# Relay_USBtoUART.net
KiCad netlist of a schematic drawn in Altium Designer
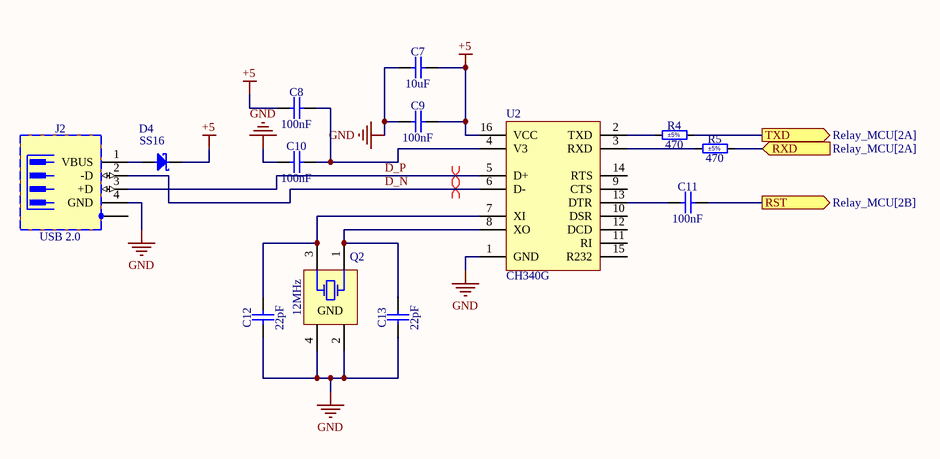
[diagram p0: Relay_USBtoUART.SchDoc]

(export (version "E")
  (design (tool "Eeschema 10.0.6"))
  (components
    (comp (ref "C7")
      (value "10uF")
      (footprint "CAPC2012X135N")
      (description "Non-polarised capacitor")
      (fields
        (field (name "PART NUMBER") "CC0805_10UF_10V_10%_X7R")
        (field (name "VOLTAGE") "10V")
        (field (name "AUTHOR") "CERN DEM JLC")
      )
      (libsource (lib "Capacitors") (part "Capacitor - non polarized"))
    )
    (comp (ref "C8")
      (value "100nF")
      (footprint "CAPC2012X135N")
      (description "Non-polarised capacitor")
      (fields
        (field (name "PART NUMBER") "CC0805_100NF_50V_10%_X7R")
        (field (name "VOLTAGE") "50V")
        (field (name "AUTHOR") "CERN DEM JLC")
      )
      (libsource (lib "Capacitors") (part "Capacitor - non polarized"))
    )
    (comp (ref "C9")
      (value "100nF")
      (footprint "CAPC2012X135N")
      (description "Non-polarised capacitor")
      (fields
        (field (name "PART NUMBER") "CC0805_100NF_50V_10%_X7R")
        (field (name "VOLTAGE") "50V")
        (field (name "AUTHOR") "CERN DEM JLC")
      )
      (libsource (lib "Capacitors") (part "Capacitor - non polarized"))
    )
    (comp (ref "C10")
      (value "100nF")
      (footprint "CAPC2012X135N")
      (description "Non-polarised capacitor")
      (fields
        (field (name "PART NUMBER") "CC0805_100NF_50V_10%_X7R")
        (field (name "VOLTAGE") "50V")
        (field (name "AUTHOR") "CERN DEM JLC")
      )
      (libsource (lib "Capacitors") (part "Capacitor - non polarized"))
    )
    (comp (ref "C11")
      (value "100nF")
      (footprint "CAPC2012X135N")
      (description "Non-polarised capacitor")
      (fields
        (field (name "PART NUMBER") "CC0805_100NF_50V_10%_X7R")
        (field (name "VOLTAGE") "50V")
        (field (name "AUTHOR") "CERN DEM JLC")
      )
      (libsource (lib "Capacitors") (part "Capacitor - non polarized"))
    )
    (comp (ref "C12")
      (value "22pF")
      (footprint "CAPC2012X88N")
      (description "Non-polarised capacitor")
      (fields
        (field (name "PART NUMBER") "CC0805_22PF_200V_5%_C0G")
        (field (name "VOLTAGE") "200V")
        (field (name "AUTHOR") "CERN DEM MR")
      )
      (libsource (lib "Capacitors") (part "Capacitor - non polarized"))
    )
    (comp (ref "C13")
      (value "22pF")
      (footprint "CAPC2012X88N")
      (description "Non-polarised capacitor")
      (fields
        (field (name "PART NUMBER") "CC0805_22PF_200V_5%_C0G")
        (field (name "VOLTAGE") "200V")
        (field (name "AUTHOR") "CERN DEM MR")
      )
      (libsource (lib "Capacitors") (part "Capacitor - non polarized"))
    )
    (comp (ref "D4")
      (value "SS16")
      (footprint "DIOM5127X229N")
      (description "Schottky Diode")
      (fields
        (field (name "VOLTAGE") "60V")
        (field (name "POWER") "1A")
        (field (name "AUTHOR") "CERN DEM JLC")
      )
      (libsource (lib "ICs And Semiconductors") (part "Diode Schottky"))
    )
    (comp (ref "J2")
      (value "USB 2.0")
      (footprint "ASSMANN_A-USBSB")
      (description "4 Pin + 1 Shield USB Receptacle")
      (fields
        (field (name "PART NUMBER") "ASSMANN_A-USBSB")
        (field (name "MANUFACTURER") "ASSMANN")
        (field (name "AUTHOR") "CERN DEM JLC")
      )
      (libsource (lib "Connectors") (part "Connector USB 4 Pin + 1Shield"))
    )
    (comp (ref "Q2")
      (value "12MHz")
      (footprint "XTAL_EPSON_TSX-3225")
      (description "Crystal 4 pins 1=XTAL Control 2=GND3=XTAL 4=GND")
      (fields
        (field (name "PART NUMBER") "XTAL_12MHZ_EPSON_TSX-3225 12.0000MF10Z-B6")
        (field (name "MANUFACTURER") "EPSON")
        (field (name "AUTHOR") "CERN DEM HF")
      )
      (libsource (lib "ICs And Semiconductors") (part "Quartz Crystal 1X 2GND 3X 4GND"))
    )
    (comp (ref "R4")
      (value "470")
      (footprint "RESC2012X60N")
      (description "Resistor - 5%")
      (fields
        (field (name "TOLERANCE") "±5%")
        (field (name "PART NUMBER") "R0805_470R_5%_0.125W_100PPM")
        (field (name "POWER") "0.125W")
        (field (name "AUTHOR") "CERN DEM JLC")
      )
      (libsource (lib "Resistors") (part "Resistor - 1%"))
    )
    (comp (ref "R5")
      (value "470")
      (footprint "RESC2012X60N")
      (description "Resistor - 5%")
      (fields
        (field (name "TOLERANCE") "±5%")
        (field (name "PART NUMBER") "R0805_470R_5%_0.125W_100PPM")
        (field (name "POWER") "0.125W")
        (field (name "AUTHOR") "CERN DEM JLC")
      )
      (libsource (lib "Resistors") (part "Resistor - 1%"))
    )
    (comp (ref "U2")
      (value "CH340G")
      (footprint "SOIC-16")
      (description "USB to UART Converter SOP16")
      (libsource (lib "IKU-LIB") (part "CH340G"))
    )
  )
  (nets
    (net (code "1") (name "+5") (class "Default")
      (node (ref "C7") (pin "2") (pinfunction "2_2") (pintype "passive"))
      (node (ref "C8") (pin "1") (pinfunction "1_1") (pintype "passive"))
      (node (ref "C9") (pin "2") (pinfunction "2_2") (pintype "passive"))
      (node (ref "D4") (pin "1") (pinfunction "C_1") (pintype "passive"))
      (node (ref "U2") (pin "16") (pinfunction "VCC_16") (pintype "passive"))
    )
    (net (code "2") (name "/D_N") (class "Default")
      (node (ref "J2") (pin "2") (pinfunction "-D_2") (pintype "bidirectional"))
      (node (ref "U2") (pin "6") (pinfunction "D-_6") (pintype "passive"))
    )
    (net (code "3") (name "/D_P") (class "Default")
      (node (ref "J2") (pin "3") (pinfunction "+D_3") (pintype "bidirectional"))
      (node (ref "U2") (pin "5") (pinfunction "D+_5") (pintype "passive"))
    )
    (net (code "4") (name "/RST") (class "Default")
      (node (ref "C11") (pin "2") (pinfunction "2_2") (pintype "passive"))
    )
    (net (code "5") (name "/RXD") (class "Default")
      (node (ref "R5") (pin "2") (pinfunction "2_2") (pintype "passive"))
    )
    (net (code "6") (name "/TXD") (class "Default")
      (node (ref "R4") (pin "2") (pinfunction "2_2") (pintype "passive"))
    )
    (net (code "7") (name "GND") (class "Default")
      (node (ref "C10") (pin "1") (pinfunction "1_1") (pintype "passive"))
      (node (ref "C12") (pin "1") (pinfunction "1_1") (pintype "passive"))
      (node (ref "C13") (pin "1") (pinfunction "1_1") (pintype "passive"))
      (node (ref "C7") (pin "1") (pinfunction "1_1") (pintype "passive"))
      (node (ref "C9") (pin "1") (pinfunction "1_1") (pintype "passive"))
      (node (ref "J2") (pin "4") (pinfunction "GND_4") (pintype "power_in"))
      (node (ref "Q2") (pin "2") (pinfunction "GND_2") (pintype "power_in"))
      (node (ref "Q2") (pin "4") (pinfunction "GND_4") (pintype "power_in"))
      (node (ref "U2") (pin "1") (pinfunction "GND_1") (pintype "passive"))
    )
    (net (code "8") (name "Net-(D4-A)") (class "Default")
      (node (ref "D4") (pin "2") (pinfunction "A_2") (pintype "passive"))
      (node (ref "J2") (pin "1") (pinfunction "VBUS_1") (pintype "power_in"))
    )
    (net (code "9") (name "Net-(U2-DTR)") (class "Default")
      (node (ref "C11") (pin "1") (pinfunction "1_1") (pintype "passive"))
      (node (ref "U2") (pin "13") (pinfunction "DTR_13") (pintype "passive"))
    )
    (net (code "10") (name "Net-(U2-RXD)") (class "Default")
      (node (ref "R5") (pin "1") (pinfunction "1_1") (pintype "passive"))
      (node (ref "U2") (pin "3") (pinfunction "RXD_3") (pintype "passive"))
    )
    (net (code "11") (name "Net-(U2-TXD)") (class "Default")
      (node (ref "R4") (pin "1") (pinfunction "1_1") (pintype "passive"))
      (node (ref "U2") (pin "2") (pinfunction "TXD_2") (pintype "passive"))
    )
    (net (code "12") (name "Net-(U2-V3)") (class "Default")
      (node (ref "C10") (pin "2") (pinfunction "2_2") (pintype "passive"))
      (node (ref "C8") (pin "2") (pinfunction "2_2") (pintype "passive"))
      (node (ref "U2") (pin "4") (pinfunction "V3_4") (pintype "passive"))
    )
    (net (code "13") (name "Net-(U2-XI)") (class "Default")
      (node (ref "C12") (pin "2") (pinfunction "2_2") (pintype "passive"))
      (node (ref "Q2") (pin "3") (pinfunction "X_3") (pintype "passive"))
      (node (ref "U2") (pin "7") (pinfunction "XI_7") (pintype "passive"))
    )
    (net (code "14") (name "Net-(U2-XO)") (class "Default")
      (node (ref "C13") (pin "2") (pinfunction "2_2") (pintype "passive"))
      (node (ref "Q2") (pin "1") (pinfunction "X_1") (pintype "passive"))
      (node (ref "U2") (pin "8") (pinfunction "XO_8") (pintype "passive"))
    )
    (net (code "15") (name "unconnected-(J2-SHIELD-Pad5)") (class "Default")
      (node (ref "J2") (pin "5") (pinfunction "SHIELD_5") (pintype "power_in"))
    )
    (net (code "16") (name "unconnected-(U2-CTS-Pad9)") (class "Default")
      (node (ref "U2") (pin "9") (pinfunction "CTS_9") (pintype "passive"))
    )
    (net (code "17") (name "unconnected-(U2-DCD-Pad12)") (class "Default")
      (node (ref "U2") (pin "12") (pinfunction "DCD_12") (pintype "passive"))
    )
    (net (code "18") (name "unconnected-(U2-DSR-Pad10)") (class "Default")
      (node (ref "U2") (pin "10") (pinfunction "DSR_10") (pintype "passive"))
    )
    (net (code "19") (name "unconnected-(U2-R232-Pad15)") (class "Default")
      (node (ref "U2") (pin "15") (pinfunction "R232_15") (pintype "passive"))
    )
    (net (code "20") (name "unconnected-(U2-RI-Pad11)") (class "Default")
      (node (ref "U2") (pin "11") (pinfunction "RI_11") (pintype "passive"))
    )
    (net (code "21") (name "unconnected-(U2-RTS-Pad14)") (class "Default")
      (node (ref "U2") (pin "14") (pinfunction "RTS_14") (pintype "passive"))
    )
  )
)
